# Candunio.net
KiCad netlist of a schematic drawn in Altium Designer
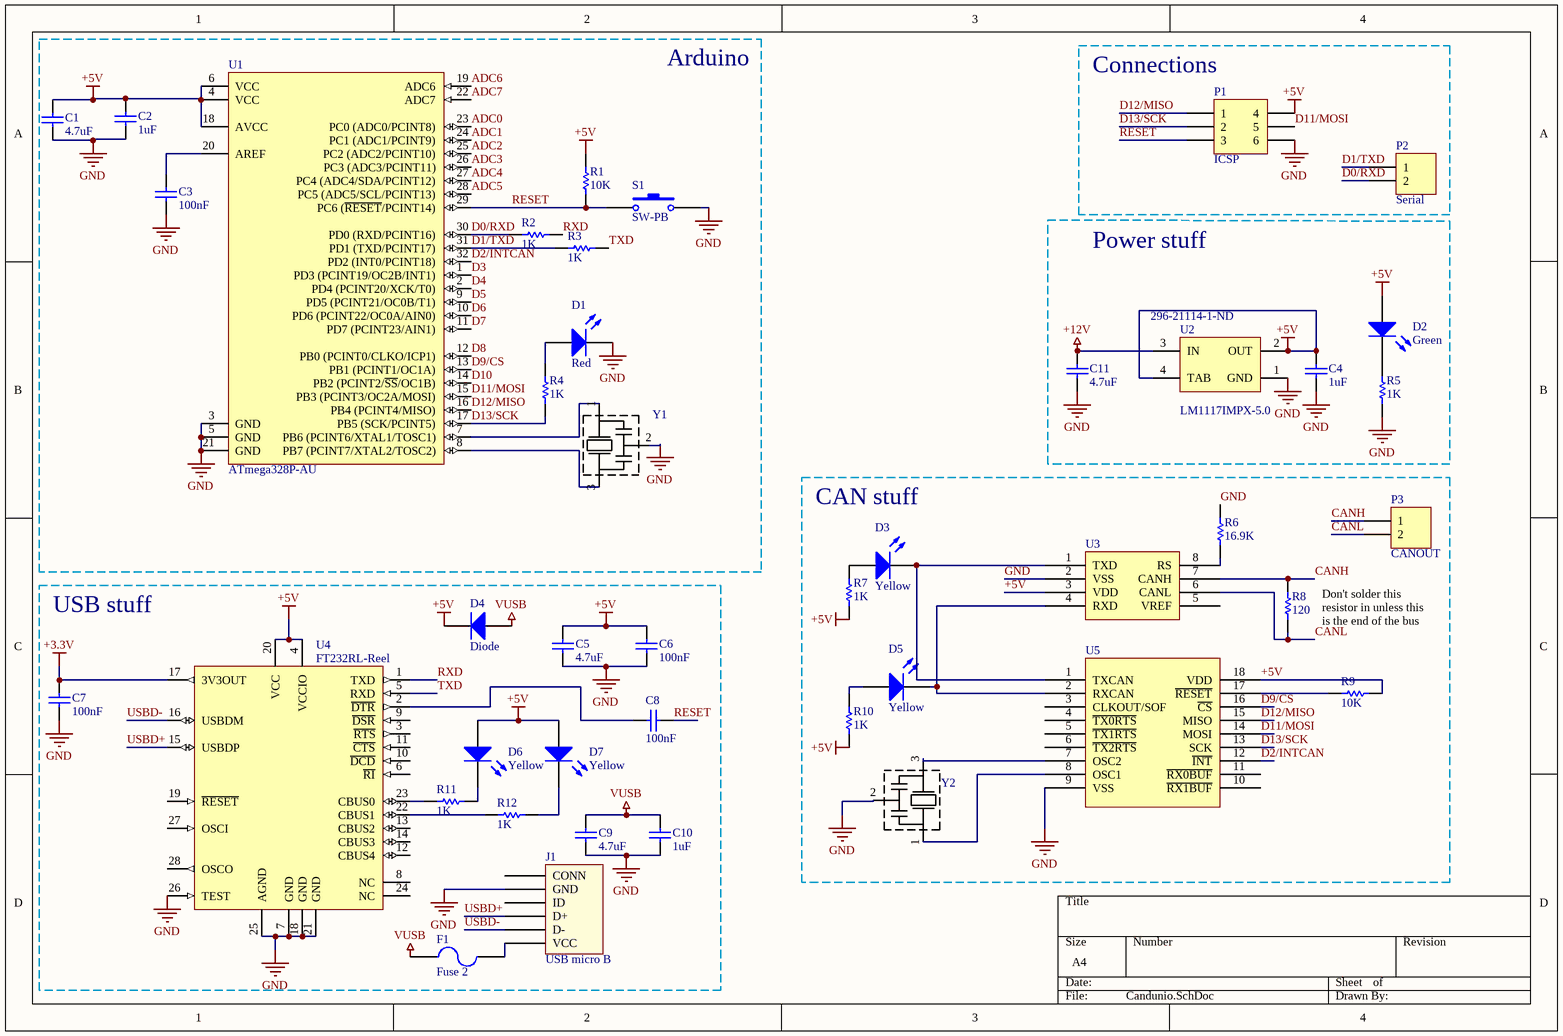
[diagram p0: Candunio.SchDoc]

(export (version "E")
  (design (tool "Eeschema 10.0.6"))
  (components
    (comp (ref "C1")
      (value "4.7uF")
      (footprint "CAPC3216X170N")
      (description "Capacitor (Semiconductor SIM Model)")
      (fields
        (field (name "MANUFACTURER") "Murata")
        (field (name "MANUFACTURER PART NUMBER") "GRM31MR71H105KA88L")
        (field (name "PUBLISHER") "Altium Limited")
      )
      (libsource (lib "Candunio v2018_7_27") (part "Cap Semi"))
    )
    (comp (ref "C2")
      (value "1uF")
      (footprint "CAPC3216X170N")
      (description "Capacitor (Semiconductor SIM Model)")
      (fields
        (field (name "MANUFACTURER") "Murata")
        (field (name "MANUFACTURER PART NUMBER") "GRM31MR71H105KA88L")
        (field (name "PUBLISHER") "Altium Limited")
      )
      (libsource (lib "Candunio v2018_7_27") (part "Cap Semi"))
    )
    (comp (ref "C3")
      (value "100nF")
      (footprint "CAPC3216X170N")
      (description "Capacitor (Semiconductor SIM Model)")
      (fields
        (field (name "MANUFACTURER") "Murata")
        (field (name "MANUFACTURER PART NUMBER") "GRM31MR71H105KA88L")
        (field (name "PUBLISHER") "Altium Limited")
      )
      (libsource (lib "Candunio v2018_7_27") (part "Cap Semi"))
    )
    (comp (ref "C4")
      (value "1uF")
      (footprint "CAPC3216X170N")
      (description "Capacitor (Semiconductor SIM Model)")
      (fields
        (field (name "MANUFACTURER") "Murata")
        (field (name "MANUFACTURER PART NUMBER") "GRM31MR71H105KA88L")
        (field (name "PUBLISHER") "Altium Limited")
      )
      (libsource (lib "Candunio v2018_7_27") (part "Cap Semi"))
    )
    (comp (ref "C5")
      (value "4.7uF")
      (footprint "CAPC3216X170N")
      (description "Capacitor (Semiconductor SIM Model)")
      (fields
        (field (name "MANUFACTURER") "Murata")
        (field (name "MANUFACTURER PART NUMBER") "GRM31MR71H105KA88L")
        (field (name "PUBLISHER") "Altium Limited")
      )
      (libsource (lib "Candunio v2018_7_27") (part "Cap Semi"))
    )
    (comp (ref "C6")
      (value "100nF")
      (footprint "CAPC3216X170N")
      (description "Capacitor (Semiconductor SIM Model)")
      (fields
        (field (name "MANUFACTURER") "Murata")
        (field (name "MANUFACTURER PART NUMBER") "GRM31MR71H105KA88L")
        (field (name "PUBLISHER") "Altium Limited")
      )
      (libsource (lib "Candunio v2018_7_27") (part "Cap Semi"))
    )
    (comp (ref "C7")
      (value "100nF")
      (footprint "CAPC3216X170N")
      (description "Capacitor (Semiconductor SIM Model)")
      (fields
        (field (name "MANUFACTURER") "Murata")
        (field (name "MANUFACTURER PART NUMBER") "GRM31MR71H105KA88L")
        (field (name "PUBLISHER") "Altium Limited")
      )
      (libsource (lib "Candunio v2018_7_27") (part "Cap Semi"))
    )
    (comp (ref "C8")
      (value "100nF")
      (footprint "CAPC3216X170N")
      (description "Capacitor (Semiconductor SIM Model)")
      (fields
        (field (name "MANUFACTURER") "Murata")
        (field (name "MANUFACTURER PART NUMBER") "GRM31MR71H105KA88L")
        (field (name "PUBLISHER") "Altium Limited")
      )
      (libsource (lib "Candunio v2018_7_27") (part "Cap Semi"))
    )
    (comp (ref "C9")
      (value "4.7uF")
      (footprint "CAPC3216X170N")
      (description "Capacitor (Semiconductor SIM Model)")
      (fields
        (field (name "MANUFACTURER") "Murata")
        (field (name "MANUFACTURER PART NUMBER") "GRM31MR71H105KA88L")
        (field (name "PUBLISHER") "Altium Limited")
      )
      (libsource (lib "Candunio v2018_7_27") (part "Cap Semi"))
    )
    (comp (ref "C10")
      (value "1uF")
      (footprint "CAPC3216X170N")
      (description "Capacitor (Semiconductor SIM Model)")
      (fields
        (field (name "MANUFACTURER") "Murata")
        (field (name "MANUFACTURER PART NUMBER") "GRM31MR71H105KA88L")
        (field (name "PUBLISHER") "Altium Limited")
      )
      (libsource (lib "Candunio v2018_7_27") (part "Cap Semi"))
    )
    (comp (ref "C11")
      (value "4.7uF")
      (footprint "CAPC3216X170N")
      (description "Capacitor (Semiconductor SIM Model)")
      (fields
        (field (name "MANUFACTURER") "Murata")
        (field (name "MANUFACTURER PART NUMBER") "GRM31MR71H105KA88L")
        (field (name "PUBLISHER") "Altium Limited")
      )
      (libsource (lib "Candunio v2018_7_27") (part "Cap Semi"))
    )
    (comp (ref "D1")
      (value "Red")
      (footprint "LEDC3216X120NRED")
      (description "Typical RED, GREEN, YELLOW, AMBER GaAs LED")
      (fields
        (field (name "MANUFACTURER") "Broadcom Avago")
        (field (name "MANUFACTURER PART NUMBER") "HSMY-C150")
        (field (name "PUBLISHER") "Altium Limited")
      )
      (libsource (lib "Miscellaneous Devices") (part "LED2"))
    )
    (comp (ref "D2")
      (value "Green")
      (footprint "LEDC3216X120NGRN")
      (description "Typical RED, GREEN, YELLOW, AMBER GaAs LED")
      (fields
        (field (name "MANUFACTURER") "Broadcom Avago")
        (field (name "MANUFACTURER PART NUMBER") "HSMG-C150")
        (field (name "PUBLISHER") "Altium Limited")
      )
      (libsource (lib "Miscellaneous Devices") (part "LED2"))
    )
    (comp (ref "D3")
      (value "Yellow")
      (footprint "LEDC3216X120NYEL")
      (description "Typical RED, GREEN, YELLOW, AMBER GaAs LED")
      (fields
        (field (name "MANUFACTURER") "Broadcom Avago")
        (field (name "MANUFACTURER PART NUMBER") "HSMY-C150")
        (field (name "PUBLISHER") "Altium Limited")
      )
      (libsource (lib "Miscellaneous Devices") (part "LED2"))
    )
    (comp (ref "D4")
      (value "Diode")
      (footprint "Integrated_Library1:DO-220AA")
      (description "Default Diode")
      (fields (field (name "PUBLISHER") "Altium Limited"))
      (libsource (lib "Miscellaneous Devices") (part "Diode"))
    )
    (comp (ref "D5")
      (value "Yellow")
      (footprint "LEDC3216X120NYEL")
      (description "Typical RED, GREEN, YELLOW, AMBER GaAs LED")
      (fields
        (field (name "MANUFACTURER") "Broadcom Avago")
        (field (name "MANUFACTURER PART NUMBER") "HSMY-C150")
        (field (name "PUBLISHER") "Altium Limited")
      )
      (libsource (lib "Miscellaneous Devices") (part "LED2"))
    )
    (comp (ref "D6")
      (value "Yellow")
      (footprint "LEDC3216X120NYEL")
      (description "Typical RED, GREEN, YELLOW, AMBER GaAs LED")
      (fields
        (field (name "MANUFACTURER") "Broadcom Avago")
        (field (name "MANUFACTURER PART NUMBER") "HSMY-C150")
        (field (name "PUBLISHER") "Altium Limited")
      )
      (libsource (lib "Miscellaneous Devices") (part "LED2"))
    )
    (comp (ref "D7")
      (value "Yellow")
      (footprint "LEDC3216X120NYEL")
      (description "Typical RED, GREEN, YELLOW, AMBER GaAs LED")
      (fields
        (field (name "MANUFACTURER") "Broadcom Avago")
        (field (name "MANUFACTURER PART NUMBER") "HSMY-C150")
        (field (name "PUBLISHER") "Altium Limited")
      )
      (libsource (lib "Miscellaneous Devices") (part "LED2"))
    )
    (comp (ref "F1")
      (value "Fuse 2")
      (footprint "Integrated_Library1:FUSC4632X85N")
      (description "Fuse")
      (fields
        (field (name "PART NUMBER") "MF-MSMF050-2")
        (field (name "MANUFACTURER") "Bourns")
        (field (name "PUBLISHER") "Altium Limited")
      )
      (libsource (lib "Miscellaneous Devices") (part "Fuse 2"))
    )
    (comp (ref "J1")
      (value "USB micro B")
      (footprint "1050170001")
      (description "CONN SM TH USB MICRO MODIFIED FOR DRILL")
      (fields (field (name "PART NUMBER") "WM1399CT-ND"))
      (libsource (lib "electronpowered") (part "1050170001"))
    )
    (comp (ref "P1")
      (value "ICSP")
      (footprint "Pin Header 2x3 TH Pitch 2.54mm")
      (description "Header, 3-Pin, Dual row")
      (fields (field (name "PUBLISHER") "Altium Limited"))
      (libsource (lib "Miscellaneous Connectors") (part "Header 3X2A"))
    )
    (comp (ref "P2")
      (value "Serial")
      (footprint "Candunio v2018_7_16:Pin Header 1x2 TH Pitch 2.54mm")
      (description "Header, 2-Pin")
      (fields (field (name "PUBLISHER") "Altium Limited"))
      (libsource (lib "Miscellaneous Connectors") (part "Header 2"))
    )
    (comp (ref "P3")
      (value "CANOUT")
      (footprint "Candunio v2018_7_16:Pin Header 1x2 TH Pitch 2.54mm")
      (description "Header, 2-Pin")
      (fields (field (name "PUBLISHER") "Altium Limited"))
      (libsource (lib "Miscellaneous Connectors") (part "Header 2"))
    )
    (comp (ref "R1")
      (value "10K")
      (footprint "RESC3216X60N")
      (description "Resistor")
      (fields
        (field (name "MANUFACTURER") "Stackpole Electronics")
        (field (name "MANUFACTURER PART NUMBER") "RNCP1206FTD1K00")
      )
      (libsource (lib "Miscellaneous Devices") (part "Res1"))
    )
    (comp (ref "R2")
      (value "1K")
      (footprint "RESC3216X60N")
      (description "Resistor")
      (fields
        (field (name "MANUFACTURER") "Stackpole Electronics")
        (field (name "MANUFACTURER PART NUMBER") "RNCP1206FTD1K00")
      )
      (libsource (lib "Miscellaneous Devices") (part "Res1"))
    )
    (comp (ref "R3")
      (value "1K")
      (footprint "RESC3216X60N")
      (description "Resistor")
      (fields
        (field (name "MANUFACTURER") "Stackpole Electronics")
        (field (name "MANUFACTURER PART NUMBER") "RNCP1206FTD1K00")
      )
      (libsource (lib "Miscellaneous Devices") (part "Res1"))
    )
    (comp (ref "R4")
      (value "1K")
      (footprint "RESC3216X60N")
      (description "Resistor")
      (fields
        (field (name "MANUFACTURER") "Stackpole Electronics")
        (field (name "MANUFACTURER PART NUMBER") "RNCP1206FTD1K00")
      )
      (libsource (lib "Miscellaneous Devices") (part "Res1"))
    )
    (comp (ref "R5")
      (value "1K")
      (footprint "RESC3216X60N")
      (description "Resistor")
      (fields
        (field (name "MANUFACTURER") "Stackpole Electronics")
        (field (name "MANUFACTURER PART NUMBER") "RNCP1206FTD1K00")
      )
      (libsource (lib "Miscellaneous Devices") (part "Res1"))
    )
    (comp (ref "R6")
      (value "16.9K")
      (footprint "RESC3216X60N")
      (description "Resistor")
      (fields
        (field (name "MANUFACTURER") "TE Connectivity Holsworthy")
        (field (name "MANUFACTURER PART NUMBER") "CRGH1206F16K9")
      )
      (libsource (lib "Miscellaneous Devices") (part "Res1"))
    )
    (comp (ref "R7")
      (value "1K")
      (footprint "RESC3216X60N")
      (description "Resistor")
      (fields
        (field (name "MANUFACTURER") "Stackpole Electronics")
        (field (name "MANUFACTURER PART NUMBER") "RNCP1206FTD1K00")
      )
      (libsource (lib "Miscellaneous Devices") (part "Res1"))
    )
    (comp (ref "R8")
      (value "120")
      (footprint "RESC3216X60N")
      (description "Resistor")
      (fields
        (field (name "MANUFACTURER") "Vishay")
        (field (name "MANUFACTURER PART NUMBER") "CRCW1206120RFKEAHP")
      )
      (libsource (lib "Miscellaneous Devices") (part "Res1"))
    )
    (comp (ref "R9")
      (value "10K")
      (footprint "RESC3216X60N")
      (description "Resistor")
      (fields
        (field (name "MANUFACTURER") "Stackpole Electronics")
        (field (name "MANUFACTURER PART NUMBER") "RNCP1206FTD10K0")
      )
      (libsource (lib "Miscellaneous Devices") (part "Res1"))
    )
    (comp (ref "R10")
      (value "1K")
      (footprint "RESC3216X60N")
      (description "Resistor")
      (fields
        (field (name "MANUFACTURER") "Stackpole Electronics")
        (field (name "MANUFACTURER PART NUMBER") "RNCP1206FTD1K00")
      )
      (libsource (lib "Miscellaneous Devices") (part "Res1"))
    )
    (comp (ref "R11")
      (value "1K")
      (footprint "RESC3216X60N")
      (description "Resistor")
      (fields
        (field (name "MANUFACTURER") "Stackpole Electronics")
        (field (name "MANUFACTURER PART NUMBER") "RNCP1206FTD1K00")
      )
      (libsource (lib "Miscellaneous Devices") (part "Res1"))
    )
    (comp (ref "R12")
      (value "1K")
      (footprint "RESC3216X60N")
      (description "Resistor")
      (fields
        (field (name "MANUFACTURER") "Stackpole Electronics")
        (field (name "MANUFACTURER PART NUMBER") "RNCP1206FTD1K00")
      )
      (libsource (lib "Miscellaneous Devices") (part "Res1"))
    )
    (comp (ref "S1")
      (value "SW-PB")
      (footprint "1206SMDswitch:SMDswitch_1206")
      (description "Switch")
      (fields
        (field (name "MANUFACTURER") "ITT C&K")
        (field (name "MANUFACTURER PART NUMBER") "KXT331LHS")
        (field (name "PUBLISHER") "Altium Limited")
      )
      (libsource (lib "Miscellaneous Devices") (part "SW-PB"))
    )
    (comp (ref "U1")
      (value "ATmega328P-AU")
      (footprint "QFP80P900X900X120-32N")
      (fields (field (name "PUBLISHER") "Altium Limited"))
      (libsource (lib "Atmel Microcontroller 8-Bit megaAVR") (part "ATmega328P-AU"))
    )
    (comp (ref "U2")
      (value "LM1117IMPX-5.0")
      (footprint "SOT230P700X180-4N")
      (description "800mA Low-Dropout Linear Regulator, 4-pin SOT-223")
      (fields
        (field (name "PARTNUMBER") "LM1117IMPX-5.0/NOPBCT-ND")
        (field (name "MANUFACTURER") "National Semiconductor")
        (field (name "SUPPLIER PART NUMBER") "296-21114-1-ND")
        (field (name "PUBLISHER") "Altium Limited")
      )
      (libsource (lib "NSC LDO") (part "LM1117IMPX-5.0"))
    )
    (comp (ref "U3")
      (value "MCP2551-E/SN")
      (footprint "SOIC127P600X175-8N")
      (description "SOIC")
      (libsource (lib "AMSComponents") (part "MCP2551-E/SN"))
    )
    (comp (ref "U4")
      (value "FT232RL-Reel")
      (footprint "SOP65P780X200-28N")
      (description "USB UART Asynchronous Serial Data Transfer Chip, SSOP-28, Tape and Reel")
      (fields
        (field (name "MANUFACTURER") "FTDI")
        (field (name "MANUFACTURER PART NUMBER") "FT232RL-REEL")
        (field (name "PUBLISHER") "Altium Limited")
      )
      (libsource (lib "FTDI Communication UART") (part "FT232RL-Reel"))
    )
    (comp (ref "U5")
      (value "MCP2515-E/ST")
      (footprint "SOIC127P1030X265-18N")
      (description "SOIC")
      (libsource (lib "AMSComponents") (part "MCP2515-E/ST"))
    )
    (comp (ref "Y1")
      (value "CSTCE16M0V53-R0")
      (footprint "CSTCE_G")
      (fields
        (field (name "MANUFACTURER") "Murata")
        (field (name "MANUFACTURER PART NUMBER") "CSTCE16M0V53C-R0")
        (field (name "TOLERANCE") "0.5%")
      )
      (libsource (lib "AMSComponents") (part "CSTCE16M0V53-R0"))
    )
    (comp (ref "Y2")
      (value "CSTCE16M0V53-R0")
      (footprint "CSTCE_G")
      (fields
        (field (name "MANUFACTURER") "Murata")
        (field (name "MANUFACTURER PART NUMBER") "CSTCE16M0V53C-R0")
        (field (name "TOLERANCE") "0.5%")
      )
      (libsource (lib "AMSComponents") (part "CSTCE16M0V53-R0"))
    )
  )
  (nets
    (net (code "1") (name "+3.3V") (class "Default")
      (node (ref "C7") (pin "2") (pinfunction "2_2") (pintype "passive"))
      (node (ref "U4") (pin "17") (pinfunction "3V3OUT_17") (pintype "output"))
    )
    (net (code "2") (name "+5V") (class "Default")
      (node (ref "C1") (pin "1") (pinfunction "1_1") (pintype "passive"))
      (node (ref "C2") (pin "2") (pinfunction "2_2") (pintype "passive"))
      (node (ref "C4") (pin "2") (pinfunction "2_2") (pintype "passive"))
      (node (ref "C5") (pin "2") (pinfunction "2_2") (pintype "passive"))
      (node (ref "C6") (pin "2") (pinfunction "2_2") (pintype "passive"))
      (node (ref "D2") (pin "1") (pinfunction "A_1") (pintype "passive"))
      (node (ref "D4") (pin "2") (pinfunction "K_2") (pintype "passive"))
      (node (ref "D6") (pin "1") (pinfunction "A_1") (pintype "passive"))
      (node (ref "D7") (pin "1") (pinfunction "A_1") (pintype "passive"))
      (node (ref "P1") (pin "4") (pinfunction "4_4") (pintype "passive"))
      (node (ref "R1") (pin "1") (pinfunction "1_1") (pintype "passive"))
      (node (ref "R10") (pin "2") (pinfunction "2_2") (pintype "passive"))
      (node (ref "R7") (pin "1") (pinfunction "1_1") (pintype "passive"))
      (node (ref "R9") (pin "2") (pinfunction "2_2") (pintype "passive"))
      (node (ref "U1") (pin "18") (pinfunction "AVCC_18") (pintype "power_in"))
      (node (ref "U1") (pin "4") (pinfunction "VCC_4") (pintype "power_in"))
      (node (ref "U1") (pin "6") (pinfunction "VCC_6") (pintype "power_in"))
      (node (ref "U2") (pin "2") (pinfunction "OUT_2") (pintype "power_in"))
      (node (ref "U2") (pin "4") (pinfunction "TAB_4") (pintype "power_in"))
      (node (ref "U3") (pin "3") (pinfunction "VDD_3") (pintype "passive"))
      (node (ref "U4") (pin "20") (pinfunction "VCC_20") (pintype "power_in"))
      (node (ref "U4") (pin "4") (pinfunction "VCCIO_4") (pintype "power_in"))
      (node (ref "U5") (pin "18") (pinfunction "VDD_18") (pintype "passive"))
    )
    (net (code "3") (name "+12V") (class "Default")
      (node (ref "C11") (pin "2") (pinfunction "2_2") (pintype "passive"))
      (node (ref "U2") (pin "3") (pinfunction "IN_3") (pintype "power_in"))
    )
    (net (code "4") (name "/ADC0") (class "Default")
      (node (ref "U1") (pin "23") (pinfunction "PC0_(ADC0/PCINT8)_23") (pintype "bidirectional"))
    )
    (net (code "5") (name "/ADC1") (class "Default")
      (node (ref "U1") (pin "24") (pinfunction "PC1_(ADC1/PCINT9)_24") (pintype "bidirectional"))
    )
    (net (code "6") (name "/ADC2") (class "Default")
      (node (ref "U1") (pin "25") (pinfunction "PC2_(ADC2/PCINT10)_25") (pintype "bidirectional"))
    )
    (net (code "7") (name "/ADC3") (class "Default")
      (node (ref "U1") (pin "26") (pinfunction "PC3_(ADC3/PCINT11)_26") (pintype "bidirectional"))
    )
    (net (code "8") (name "/ADC4") (class "Default")
      (node (ref "U1") (pin "27") (pinfunction "PC4_(ADC4/SDA/PCINT12)_27") (pintype "bidirectional"))
    )
    (net (code "9") (name "/ADC5") (class "Default")
      (node (ref "U1") (pin "28") (pinfunction "PC5_(ADC5/SCL/PCINT13)_28") (pintype "bidirectional"))
    )
    (net (code "10") (name "/ADC6") (class "Default")
      (node (ref "U1") (pin "19") (pinfunction "ADC6_19") (pintype "input"))
    )
    (net (code "11") (name "/ADC7") (class "Default")
      (node (ref "U1") (pin "22") (pinfunction "ADC7_22") (pintype "input"))
    )
    (net (code "12") (name "/CANH") (class "Default")
      (node (ref "P3") (pin "1") (pinfunction "1_1") (pintype "passive"))
      (node (ref "R8") (pin "1") (pinfunction "1_1") (pintype "passive"))
      (node (ref "U3") (pin "7") (pinfunction "CANH_7") (pintype "passive"))
    )
    (net (code "13") (name "/CANL") (class "Default")
      (node (ref "P3") (pin "2") (pinfunction "2_2") (pintype "passive"))
      (node (ref "R8") (pin "2") (pinfunction "2_2") (pintype "passive"))
      (node (ref "U3") (pin "6") (pinfunction "CANL_6") (pintype "passive"))
    )
    (net (code "14") (name "/D0{slash}RXD") (class "Default")
      (node (ref "P2") (pin "2") (pinfunction "2_2") (pintype "passive"))
      (node (ref "R2") (pin "1") (pinfunction "1_1") (pintype "passive"))
      (node (ref "U1") (pin "30") (pinfunction "PD0_(RXD/PCINT16)_30") (pintype "bidirectional"))
    )
    (net (code "15") (name "/D1{slash}TXD") (class "Default")
      (node (ref "P2") (pin "1") (pinfunction "1_1") (pintype "passive"))
      (node (ref "R3") (pin "1") (pinfunction "1_1") (pintype "passive"))
      (node (ref "U1") (pin "31") (pinfunction "PD1_(TXD/PCINT17)_31") (pintype "bidirectional"))
    )
    (net (code "16") (name "/D2{slash}INTCAN") (class "Default")
      (node (ref "U1") (pin "32") (pinfunction "PD2_(INT0/PCINT18)_32") (pintype "bidirectional"))
      (node (ref "U5") (pin "12") (pinfunction "~{INT}_12") (pintype "passive"))
    )
    (net (code "17") (name "/D3") (class "Default")
      (node (ref "U1") (pin "1") (pinfunction "PD3_(PCINT19/OC2B/INT1)_1") (pintype "bidirectional"))
    )
    (net (code "18") (name "/D4") (class "Default")
      (node (ref "U1") (pin "2") (pinfunction "PD4_(PCINT20/XCK/T0)_2") (pintype "bidirectional"))
    )
    (net (code "19") (name "/D5") (class "Default")
      (node (ref "U1") (pin "9") (pinfunction "PD5_(PCINT21/OC0B/T1)_9") (pintype "bidirectional"))
    )
    (net (code "20") (name "/D6") (class "Default")
      (node (ref "U1") (pin "10") (pinfunction "PD6_(PCINT22/OC0A/AIN0)_10") (pintype "bidirectional"))
    )
    (net (code "21") (name "/D7") (class "Default")
      (node (ref "U1") (pin "11") (pinfunction "PD7_(PCINT23/AIN1)_11") (pintype "bidirectional"))
    )
    (net (code "22") (name "/D8") (class "Default")
      (node (ref "U1") (pin "12") (pinfunction "PB0_(PCINT0/CLKO/ICP1)_12") (pintype "bidirectional"))
    )
    (net (code "23") (name "/D9{slash}CS") (class "Default")
      (node (ref "U1") (pin "13") (pinfunction "PB1_(PCINT1/OC1A)_13") (pintype "bidirectional"))
      (node (ref "U5") (pin "16") (pinfunction "~{CS}_16") (pintype "passive"))
    )
    (net (code "24") (name "/D10") (class "Default")
      (node (ref "U1") (pin "14") (pinfunction "PB2_(PCINT2/~{SS}/OC1B)_14") (pintype "bidirectional"))
    )
    (net (code "25") (name "/D11{slash}MOSI") (class "Default")
      (node (ref "P1") (pin "5") (pinfunction "5_5") (pintype "passive"))
      (node (ref "U1") (pin "15") (pinfunction "PB3_(PCINT3/OC2A/MOSI)_15") (pintype "bidirectional"))
      (node (ref "U5") (pin "14") (pinfunction "MOSI_14") (pintype "passive"))
    )
    (net (code "26") (name "/D12{slash}MISO") (class "Default")
      (node (ref "P1") (pin "1") (pinfunction "1_1") (pintype "passive"))
      (node (ref "U1") (pin "16") (pinfunction "PB4_(PCINT4/MISO)_16") (pintype "bidirectional"))
      (node (ref "U5") (pin "15") (pinfunction "MISO_15") (pintype "passive"))
    )
    (net (code "27") (name "/D13{slash}SCK") (class "Default")
      (node (ref "P1") (pin "2") (pinfunction "2_2") (pintype "passive"))
      (node (ref "R4") (pin "2") (pinfunction "2_2") (pintype "passive"))
      (node (ref "U1") (pin "17") (pinfunction "PB5_(SCK/PCINT5)_17") (pintype "bidirectional"))
      (node (ref "U5") (pin "13") (pinfunction "SCK_13") (pintype "passive"))
    )
    (net (code "28") (name "/RESET") (class "Default")
      (node (ref "C8") (pin "2") (pinfunction "2_2") (pintype "passive"))
      (node (ref "P1") (pin "3") (pinfunction "3_3") (pintype "passive"))
      (node (ref "R1") (pin "2") (pinfunction "2_2") (pintype "passive"))
      (node (ref "S1") (pin "1") (pinfunction "1_1") (pintype "passive"))
      (node (ref "U1") (pin "29") (pinfunction "PC6_(~{RESET}/PCINT14)_29") (pintype "bidirectional"))
    )
    (net (code "29") (name "/RXD") (class "Default")
      (node (ref "R2") (pin "2") (pinfunction "2_2") (pintype "passive"))
      (node (ref "U4") (pin "1") (pinfunction "TXD_1") (pintype "output"))
    )
    (net (code "30") (name "/TXD") (class "Default")
      (node (ref "R3") (pin "2") (pinfunction "2_2") (pintype "passive"))
      (node (ref "U4") (pin "5") (pinfunction "RXD_5") (pintype "input"))
    )
    (net (code "31") (name "/USBD+") (class "Default")
      (node (ref "J1") (pin "3") (pinfunction "D+_3") (pintype "passive"))
      (node (ref "U4") (pin "15") (pinfunction "USBDP_15") (pintype "bidirectional"))
    )
    (net (code "32") (name "/USBD-") (class "Default")
      (node (ref "J1") (pin "2") (pinfunction "D-_2") (pintype "passive"))
      (node (ref "U4") (pin "16") (pinfunction "USBDM_16") (pintype "bidirectional"))
    )
    (net (code "33") (name "GND") (class "Default")
      (node (ref "C1") (pin "2") (pinfunction "2_2") (pintype "passive"))
      (node (ref "C10") (pin "1") (pinfunction "1_1") (pintype "passive"))
      (node (ref "C11") (pin "1") (pinfunction "1_1") (pintype "passive"))
      (node (ref "C2") (pin "1") (pinfunction "1_1") (pintype "passive"))
      (node (ref "C3") (pin "1") (pinfunction "1_1") (pintype "passive"))
      (node (ref "C4") (pin "1") (pinfunction "1_1") (pintype "passive"))
      (node (ref "C5") (pin "1") (pinfunction "1_1") (pintype "passive"))
      (node (ref "C6") (pin "1") (pinfunction "1_1") (pintype "passive"))
      (node (ref "C7") (pin "1") (pinfunction "1_1") (pintype "passive"))
      (node (ref "C9") (pin "1") (pinfunction "1_1") (pintype "passive"))
      (node (ref "D1") (pin "2") (pinfunction "K_2") (pintype "passive"))
      (node (ref "J1") (pin "5") (pinfunction "GND_5") (pintype "passive"))
      (node (ref "P1") (pin "6") (pinfunction "6_6") (pintype "passive"))
      (node (ref "R5") (pin "2") (pinfunction "2_2") (pintype "passive"))
      (node (ref "R6") (pin "1") (pinfunction "1_1") (pintype "passive"))
      (node (ref "S1") (pin "2") (pinfunction "2_2") (pintype "passive"))
      (node (ref "U1") (pin "21") (pinfunction "GND_21") (pintype "power_in"))
      (node (ref "U1") (pin "3") (pinfunction "GND_3") (pintype "power_in"))
      (node (ref "U1") (pin "5") (pinfunction "GND_5") (pintype "power_in"))
      (node (ref "U2") (pin "1") (pinfunction "GND_1") (pintype "power_in"))
      (node (ref "U3") (pin "2") (pinfunction "VSS_2") (pintype "passive"))
      (node (ref "U4") (pin "18") (pinfunction "GND_18") (pintype "power_in"))
      (node (ref "U4") (pin "21") (pinfunction "GND_21") (pintype "power_in"))
      (node (ref "U4") (pin "25") (pinfunction "AGND_25") (pintype "power_in"))
      (node (ref "U4") (pin "26") (pinfunction "TEST_26") (pintype "input"))
      (node (ref "U4") (pin "7") (pinfunction "GND_7") (pintype "power_in"))
      (node (ref "U5") (pin "9") (pinfunction "VSS_9") (pintype "passive"))
      (node (ref "Y1") (pin "2") (pinfunction "2_2") (pintype "passive"))
      (node (ref "Y2") (pin "2") (pinfunction "2_2") (pintype "passive"))
    )
    (net (code "34") (name "Net-(D1-A)") (class "Default")
      (node (ref "D1") (pin "1") (pinfunction "A_1") (pintype "passive"))
      (node (ref "R4") (pin "1") (pinfunction "1_1") (pintype "passive"))
    )
    (net (code "35") (name "Net-(D2-K)") (class "Default")
      (node (ref "D2") (pin "2") (pinfunction "K_2") (pintype "passive"))
      (node (ref "R5") (pin "1") (pinfunction "1_1") (pintype "passive"))
    )
    (net (code "36") (name "Net-(D3-A)") (class "Default")
      (node (ref "D3") (pin "1") (pinfunction "A_1") (pintype "passive"))
      (node (ref "R7") (pin "2") (pinfunction "2_2") (pintype "passive"))
    )
    (net (code "37") (name "Net-(D3-K)") (class "Default")
      (node (ref "D3") (pin "2") (pinfunction "K_2") (pintype "passive"))
      (node (ref "U3") (pin "1") (pinfunction "TXD_1") (pintype "passive"))
      (node (ref "U5") (pin "1") (pinfunction "TXCAN_1") (pintype "passive"))
    )
    (net (code "38") (name "Net-(D5-A)") (class "Default")
      (node (ref "D5") (pin "1") (pinfunction "A_1") (pintype "passive"))
      (node (ref "R10") (pin "1") (pinfunction "1_1") (pintype "passive"))
    )
    (net (code "39") (name "Net-(D5-K)") (class "Default")
      (node (ref "D5") (pin "2") (pinfunction "K_2") (pintype "passive"))
      (node (ref "U3") (pin "4") (pinfunction "RXD_4") (pintype "passive"))
      (node (ref "U5") (pin "2") (pinfunction "RXCAN_2") (pintype "passive"))
    )
    (net (code "40") (name "Net-(D6-K)") (class "Default")
      (node (ref "D6") (pin "2") (pinfunction "K_2") (pintype "passive"))
      (node (ref "R11") (pin "2") (pinfunction "2_2") (pintype "passive"))
    )
    (net (code "41") (name "Net-(D7-K)") (class "Default")
      (node (ref "D7") (pin "2") (pinfunction "K_2") (pintype "passive"))
      (node (ref "R12") (pin "2") (pinfunction "2_2") (pintype "passive"))
    )
    (net (code "42") (name "Net-(J1-VCC)") (class "Default")
      (node (ref "F1") (pin "2") (pinfunction "2_2") (pintype "passive"))
      (node (ref "J1") (pin "1") (pinfunction "VCC_1") (pintype "passive"))
    )
    (net (code "43") (name "Net-(U1-AREF)") (class "Default")
      (node (ref "C3") (pin "2") (pinfunction "2_2") (pintype "passive"))
      (node (ref "U1") (pin "20") (pinfunction "AREF_20") (pintype "passive"))
    )
    (net (code "44") (name "Net-(U1-PB6_(PCINT6{slash}XTAL1{slash}TOSC1))") (class "Default")
      (node (ref "U1") (pin "7") (pinfunction "PB6_(PCINT6/XTAL1/TOSC1)_7") (pintype "bidirectional"))
      (node (ref "Y1") (pin "1") (pinfunction "1_1") (pintype "passive"))
    )
    (net (code "45") (name "Net-(U1-PB7_(PCINT7{slash}XTAL2{slash}TOSC2))") (class "Default")
      (node (ref "U1") (pin "8") (pinfunction "PB7_(PCINT7/XTAL2/TOSC2)_8") (pintype "bidirectional"))
      (node (ref "Y1") (pin "3") (pinfunction "3_3") (pintype "passive"))
    )
    (net (code "46") (name "Net-(U3-RS)") (class "Default")
      (node (ref "R6") (pin "2") (pinfunction "2_2") (pintype "passive"))
      (node (ref "U3") (pin "8") (pinfunction "RS_8") (pintype "passive"))
    )
    (net (code "47") (name "Net-(U4-CBUS0)") (class "Default")
      (node (ref "R11") (pin "1") (pinfunction "1_1") (pintype "passive"))
      (node (ref "U4") (pin "23") (pinfunction "CBUS0_23") (pintype "bidirectional"))
    )
    (net (code "48") (name "Net-(U4-CBUS1)") (class "Default")
      (node (ref "R12") (pin "1") (pinfunction "1_1") (pintype "passive"))
      (node (ref "U4") (pin "22") (pinfunction "CBUS1_22") (pintype "bidirectional"))
    )
    (net (code "49") (name "Net-(U4-~{DTR})") (class "Default")
      (node (ref "C8") (pin "1") (pinfunction "1_1") (pintype "passive"))
      (node (ref "U4") (pin "2") (pinfunction "~{DTR}_2") (pintype "output"))
    )
    (net (code "50") (name "Net-(U5-OSC1)") (class "Default")
      (node (ref "U5") (pin "8") (pinfunction "OSC1_8") (pintype "passive"))
      (node (ref "Y2") (pin "1") (pinfunction "1_1") (pintype "passive"))
    )
    (net (code "51") (name "Net-(U5-OSC2)") (class "Default")
      (node (ref "U5") (pin "7") (pinfunction "OSC2_7") (pintype "passive"))
      (node (ref "Y2") (pin "3") (pinfunction "3_3") (pintype "passive"))
    )
    (net (code "52") (name "Net-(U5-~{RESET})") (class "Default")
      (node (ref "R9") (pin "1") (pinfunction "1_1") (pintype "passive"))
      (node (ref "U5") (pin "17") (pinfunction "~{RESET}_17") (pintype "passive"))
    )
    (net (code "53") (name "VUSB") (class "Default")
      (node (ref "C10") (pin "2") (pinfunction "2_2") (pintype "passive"))
      (node (ref "C9") (pin "2") (pinfunction "2_2") (pintype "passive"))
      (node (ref "D4") (pin "1") (pinfunction "A_1") (pintype "passive"))
      (node (ref "F1") (pin "1") (pinfunction "1_1") (pintype "passive"))
    )
    (net (code "54") (name "unconnected-(J1-CONN-Pad0)") (class "Default")
      (node (ref "J1") (pin "0") (pinfunction "CONN_0") (pintype "passive"))
    )
    (net (code "55") (name "unconnected-(J1-ID-Pad4)") (class "Default")
      (node (ref "J1") (pin "4") (pinfunction "ID_4") (pintype "passive"))
    )
    (net (code "56") (name "unconnected-(U3-VREF-Pad5)") (class "Default")
      (node (ref "U3") (pin "5") (pinfunction "VREF_5") (pintype "passive"))
    )
    (net (code "57") (name "unconnected-(U4-CBUS2-Pad13)") (class "Default")
      (node (ref "U4") (pin "13") (pinfunction "CBUS2_13") (pintype "bidirectional"))
    )
    (net (code "58") (name "unconnected-(U4-CBUS3-Pad14)") (class "Default")
      (node (ref "U4") (pin "14") (pinfunction "CBUS3_14") (pintype "bidirectional"))
    )
    (net (code "59") (name "unconnected-(U4-CBUS4-Pad12)") (class "Default")
      (node (ref "U4") (pin "12") (pinfunction "CBUS4_12") (pintype "bidirectional"))
    )
    (net (code "60") (name "unconnected-(U4-NC-Pad8)") (class "Default")
      (node (ref "U4") (pin "8") (pinfunction "NC_8") (pintype "passive"))
    )
    (net (code "61") (name "unconnected-(U4-NC-Pad24)") (class "Default")
      (node (ref "U4") (pin "24") (pinfunction "NC_24") (pintype "passive"))
    )
    (net (code "62") (name "unconnected-(U4-OSCI-Pad27)") (class "Default")
      (node (ref "U4") (pin "27") (pinfunction "OSCI_27") (pintype "input"))
    )
    (net (code "63") (name "unconnected-(U4-OSCO-Pad28)") (class "Default")
      (node (ref "U4") (pin "28") (pinfunction "OSCO_28") (pintype "output"))
    )
    (net (code "64") (name "unconnected-(U4-~{CTS}-Pad11)") (class "Default")
      (node (ref "U4") (pin "11") (pinfunction "~{CTS}_11") (pintype "input"))
    )
    (net (code "65") (name "unconnected-(U4-~{DCD}-Pad10)") (class "Default")
      (node (ref "U4") (pin "10") (pinfunction "~{DCD}_10") (pintype "input"))
    )
    (net (code "66") (name "unconnected-(U4-~{DSR}-Pad9)") (class "Default")
      (node (ref "U4") (pin "9") (pinfunction "~{DSR}_9") (pintype "input"))
    )
    (net (code "67") (name "unconnected-(U4-~{RESET}-Pad19)") (class "Default")
      (node (ref "U4") (pin "19") (pinfunction "~{RESET}_19") (pintype "input"))
    )
    (net (code "68") (name "unconnected-(U4-~{RI}-Pad6)") (class "Default")
      (node (ref "U4") (pin "6") (pinfunction "~{RI}_6") (pintype "input"))
    )
    (net (code "69") (name "unconnected-(U4-~{RTS}-Pad3)") (class "Default")
      (node (ref "U4") (pin "3") (pinfunction "~{RTS}_3") (pintype "output"))
    )
    (net (code "70") (name "unconnected-(U5-CLKOUT{slash}SOF-Pad3)") (class "Default")
      (node (ref "U5") (pin "3") (pinfunction "CLKOUT/SOF_3") (pintype "passive"))
    )
    (net (code "71") (name "unconnected-(U5-~{RX0BUF}-Pad11)") (class "Default")
      (node (ref "U5") (pin "11") (pinfunction "~{RX0BUF}_11") (pintype "passive"))
    )
    (net (code "72") (name "unconnected-(U5-~{RX1BUF}-Pad10)") (class "Default")
      (node (ref "U5") (pin "10") (pinfunction "~{RX1BUF}_10") (pintype "passive"))
    )
    (net (code "73") (name "unconnected-(U5-~{TX0RTS}-Pad4)") (class "Default")
      (node (ref "U5") (pin "4") (pinfunction "~{TX0RTS}_4") (pintype "passive"))
    )
    (net (code "74") (name "unconnected-(U5-~{TX1RTS}-Pad5)") (class "Default")
      (node (ref "U5") (pin "5") (pinfunction "~{TX1RTS}_5") (pintype "passive"))
    )
    (net (code "75") (name "unconnected-(U5-~{TX2RTS}-Pad6)") (class "Default")
      (node (ref "U5") (pin "6") (pinfunction "~{TX2RTS}_6") (pintype "passive"))
    )
  )
)
